# Power_Circuits.net
KiCad netlist of a schematic drawn in Altium Designer
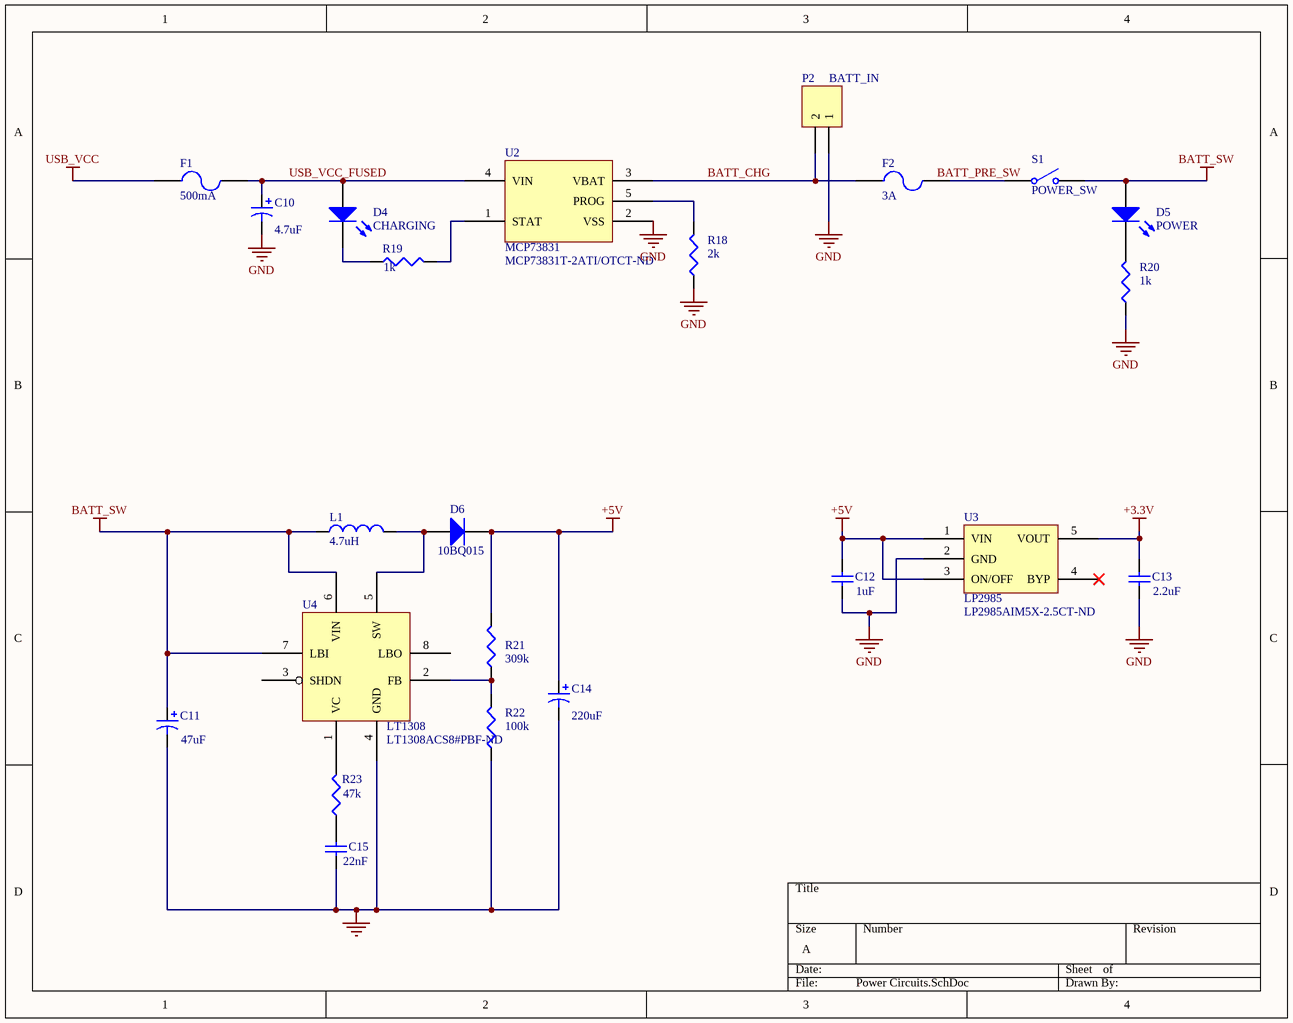
[diagram p0: Power Circuits.SchDoc]

(export (version "E")
  (design (tool "Eeschema 10.0.6"))
  (components
    (comp (ref "C10")
      (value "4.7uF")
      (footprint "TC7343-2917")
      (description "Polarized Capacitor (Surface Mount)")
      (fields (field (name "Comment") "Cap Pol3") (field (name "PUBLISHER") "Altium Limited"))
      (libsource (lib "Miscellaneous Devices") (part "Cap Pol3"))
    )
    (comp (ref "C11")
      (value "47uF")
      (footprint "TC6032-2412")
      (description "Polarized Capacitor (Surface Mount)")
      (fields (field (name "Comment") "Cap Pol3") (field (name "PUBLISHER") "Altium Limited"))
      (libsource (lib "Miscellaneous Devices") (part "Cap Pol3"))
    )
    (comp (ref "C12")
      (value "1uF")
      (footprint "C1206")
      (description "Capacitor (Semiconductor SIM Model)")
      (fields (field (name "Comment") "Cap Semi") (field (name "PUBLISHER") "Altium Limited"))
      (libsource (lib "Miscellaneous Devices") (part "Cap Semi"))
    )
    (comp (ref "C13")
      (value "2.2uF")
      (footprint "C1206")
      (description "Capacitor (Semiconductor SIM Model)")
      (fields (field (name "Comment") "Cap Semi") (field (name "PUBLISHER") "Altium Limited"))
      (libsource (lib "Miscellaneous Devices") (part "Cap Semi"))
    )
    (comp (ref "C14")
      (value "220uF")
      (footprint "TC7343-2917")
      (description "Polarized Capacitor (Surface Mount)")
      (fields (field (name "Comment") "Cap Pol3") (field (name "PUBLISHER") "Altium Limited"))
      (libsource (lib "Miscellaneous Devices") (part "Cap Pol3"))
    )
    (comp (ref "C15")
      (value "22nF")
      (footprint "C1206")
      (description "Capacitor (Semiconductor SIM Model)")
      (fields (field (name "Comment") "Cap Semi") (field (name "PUBLISHER") "Altium Limited"))
      (libsource (lib "Miscellaneous Devices") (part "Cap Semi"))
    )
    (comp (ref "D4")
      (value "CHARGING")
      (footprint "HDR1X2")
      (description "Typical BLUE SiC LED")
      (fields (field (name "PUBLISHER") "Altium Limited"))
      (libsource (lib "Miscellaneous Devices") (part "LED3"))
    )
    (comp (ref "D5")
      (value "POWER")
      (footprint "HDR1X2")
      (description "Typical BLUE SiC LED")
      (fields (field (name "PUBLISHER") "Altium Limited"))
      (libsource (lib "Miscellaneous Devices") (part "LED3"))
    )
    (comp (ref "D6")
      (value "10BQ015")
      (footprint "DSO-C2/X2.3")
      (description "Default Diode")
      (fields (field (name "PUBLISHER") "Altium Limited"))
      (libsource (lib "Miscellaneous Devices") (part "Diode"))
    )
    (comp (ref "F1")
      (value "500mA")
      (footprint "RESC3216M")
      (description "Fuse")
      (fields (field (name "PUBLISHER") "Altium Limited"))
      (libsource (lib "Miscellaneous Devices") (part "Fuse 2"))
    )
    (comp (ref "F2")
      (value "3A")
      (footprint "RESC3216M")
      (description "Fuse")
      (fields (field (name "PUBLISHER") "Altium Limited"))
      (libsource (lib "Miscellaneous Devices") (part "Fuse 2"))
    )
    (comp (ref "L1")
      (value "4.7uH")
      (footprint "MURATA SMT INDUCTOR")
      (description "Inductor")
      (fields (field (name "PUBLISHER") "Altium Limited"))
      (libsource (lib "Miscellaneous Devices") (part "Inductor"))
    )
    (comp (ref "P2")
      (value "BATT_IN")
      (footprint "2MM JST PH - 2 PIN VERT")
      (description "Header, 2-Pin")
      (fields (field (name "PUBLISHER") "Altium Limited"))
      (libsource (lib "Miscellaneous Connectors") (part "Header 2"))
    )
    (comp (ref "R18")
      (value "2k")
      (footprint "RESC3216M")
      (description "Resistor")
      (fields (field (name "Comment") "Res3") (field (name "PUBLISHER") "Altium Limited"))
      (libsource (lib "Miscellaneous Devices") (part "Res3"))
    )
    (comp (ref "R19")
      (value "1k")
      (footprint "RESC3216M")
      (description "Resistor")
      (fields (field (name "Comment") "Res3") (field (name "PUBLISHER") "Altium Limited"))
      (libsource (lib "Miscellaneous Devices") (part "Res3"))
    )
    (comp (ref "R20")
      (value "1k")
      (footprint "RESC3216M")
      (description "Resistor")
      (fields (field (name "Comment") "Res3") (field (name "PUBLISHER") "Altium Limited"))
      (libsource (lib "Miscellaneous Devices") (part "Res3"))
    )
    (comp (ref "R21")
      (value "309k")
      (footprint "RESC3216M")
      (description "Resistor")
      (fields (field (name "Comment") "Res3") (field (name "PUBLISHER") "Altium Limited"))
      (libsource (lib "Miscellaneous Devices") (part "Res3"))
    )
    (comp (ref "R22")
      (value "100k")
      (footprint "RESC3216M")
      (description "Resistor")
      (fields (field (name "Comment") "Res3") (field (name "PUBLISHER") "Altium Limited"))
      (libsource (lib "Miscellaneous Devices") (part "Res3"))
    )
    (comp (ref "R23")
      (value "47k")
      (footprint "RESC3216M")
      (description "Resistor")
      (fields (field (name "Comment") "Res3") (field (name "PUBLISHER") "Altium Limited"))
      (libsource (lib "Miscellaneous Devices") (part "Res3"))
    )
    (comp (ref "S1")
      (value "POWER_SW")
      (footprint "DPDT_PUSHBUTTON_SWITCH")
      (description "Single-Pole, Single-Throw Switch")
      (fields (field (name "PUBLISHER") "Altium Limited"))
      (libsource (lib "Miscellaneous Devices") (part "SW-SPST"))
    )
    (comp (ref "U2")
      (value "MCP73831")
      (footprint "SOT23-5AM")
      (fields (field (name "SUPPLIER PART NUMBER 1") "MCP73831T-2ATI/OTCT-ND"))
      (libsource (lib "Altium Footprints") (part "MCP73831"))
    )
    (comp (ref "U3")
      (value "LP2985")
      (footprint "SOT23-5AM")
      (fields (field (name "SUPPLIER PART NUMBER 1") "LP2985AIM5X-2.5CT-ND"))
      (libsource (lib "Altium Footprints") (part "LP2985"))
    )
    (comp (ref "U4")
      (value "LT1308")
      (footprint "SOIC127P600-8AM")
      (fields (field (name "SUPPLIER PART NUMBER 1") "LT1308ACS8#PBF-ND"))
      (libsource (lib "Altium Footprints") (part "LT1308"))
    )
  )
  (nets
    (net (code "1") (name "+3.3V") (class "Default")
      (node (ref "C13") (pin "2") (pinfunction "2_2") (pintype "passive"))
      (node (ref "U3") (pin "5") (pinfunction "VOUT_5") (pintype "passive"))
    )
    (net (code "2") (name "+5V") (class "Default")
      (node (ref "C12") (pin "2") (pinfunction "2_2") (pintype "passive"))
      (node (ref "C14") (pin "1") (pinfunction "1_1") (pintype "passive"))
      (node (ref "D6") (pin "2") (pinfunction "K_2") (pintype "passive"))
      (node (ref "R21") (pin "2") (pinfunction "2_2") (pintype "passive"))
      (node (ref "U3") (pin "1") (pinfunction "VIN_1") (pintype "passive"))
      (node (ref "U3") (pin "3") (pinfunction "ON/OFF_3") (pintype "passive"))
    )
    (net (code "3") (name "/BATT_CHG") (class "Default")
      (node (ref "F2") (pin "1") (pinfunction "1_1") (pintype "passive"))
      (node (ref "P2") (pin "2") (pinfunction "2_2") (pintype "passive"))
      (node (ref "U2") (pin "3") (pinfunction "VBAT_3") (pintype "passive"))
    )
    (net (code "5") (name "/USB_VCC_FUSED") (class "Default")
      (node (ref "C10") (pin "1") (pinfunction "1_1") (pintype "passive"))
      (node (ref "D4") (pin "1") (pinfunction "A_1") (pintype "passive"))
      (node (ref "F1") (pin "2") (pinfunction "2_2") (pintype "passive"))
      (node (ref "U2") (pin "4") (pinfunction "VIN_4") (pintype "passive"))
    )
    (net (code "6") (name "BATT_SW") (class "Default")
      (node (ref "C11") (pin "1") (pinfunction "1_1") (pintype "passive"))
      (node (ref "D5") (pin "1") (pinfunction "A_1") (pintype "passive"))
      (node (ref "L1") (pin "1") (pinfunction "1_1") (pintype "passive"))
      (node (ref "S1") (pin "2") (pinfunction "NO_2") (pintype "passive"))
      (node (ref "U4") (pin "6") (pinfunction "VIN_6") (pintype "passive"))
      (node (ref "U4") (pin "7") (pinfunction "LBI_7") (pintype "passive"))
    )
    (net (code "7") (name "GND") (class "Default")
      (node (ref "C10") (pin "2") (pinfunction "2_2") (pintype "passive"))
      (node (ref "C11") (pin "2") (pinfunction "2_2") (pintype "passive"))
      (node (ref "C12") (pin "1") (pinfunction "1_1") (pintype "passive"))
      (node (ref "C13") (pin "1") (pinfunction "1_1") (pintype "passive"))
      (node (ref "C14") (pin "2") (pinfunction "2_2") (pintype "passive"))
      (node (ref "C15") (pin "1") (pinfunction "1_1") (pintype "passive"))
      (node (ref "P2") (pin "1") (pinfunction "1_1") (pintype "passive"))
      (node (ref "R18") (pin "1") (pinfunction "1_1") (pintype "passive"))
      (node (ref "R20") (pin "1") (pinfunction "1_1") (pintype "passive"))
      (node (ref "R22") (pin "1") (pinfunction "1_1") (pintype "passive"))
      (node (ref "U2") (pin "2") (pinfunction "VSS_2") (pintype "passive"))
      (node (ref "U3") (pin "2") (pinfunction "GND_2") (pintype "passive"))
      (node (ref "U4") (pin "4") (pinfunction "GND_4") (pintype "passive"))
    )
    (net (code "8") (name "Net-(C15-Pad2)") (class "Default")
      (node (ref "C15") (pin "2") (pinfunction "2_2") (pintype "passive"))
      (node (ref "R23") (pin "1") (pinfunction "1_1") (pintype "passive"))
    )
    (net (code "9") (name "Net-(D4-K)") (class "Default")
      (node (ref "D4") (pin "2") (pinfunction "K_2") (pintype "passive"))
      (node (ref "R19") (pin "1") (pinfunction "1_1") (pintype "passive"))
    )
    (net (code "10") (name "Net-(D5-K)") (class "Default")
      (node (ref "D5") (pin "2") (pinfunction "K_2") (pintype "passive"))
      (node (ref "R20") (pin "2") (pinfunction "2_2") (pintype "passive"))
    )
    (net (code "11") (name "Net-(D6-A)") (class "Default")
      (node (ref "D6") (pin "1") (pinfunction "A_1") (pintype "passive"))
      (node (ref "L1") (pin "2") (pinfunction "2_2") (pintype "passive"))
      (node (ref "U4") (pin "5") (pinfunction "SW_5") (pintype "passive"))
    )
    (net (code "12") (name "Net-(S1-COMMON)") (class "Default")
      (node (ref "F2") (pin "2") (pinfunction "2_2") (pintype "passive"))
      (node (ref "S1") (pin "1") (pinfunction "COMMON_1") (pintype "passive"))
    )
    (net (code "13") (name "Net-(U2-PROG)") (class "Default")
      (node (ref "R18") (pin "2") (pinfunction "2_2") (pintype "passive"))
      (node (ref "U2") (pin "5") (pinfunction "PROG_5") (pintype "passive"))
    )
    (net (code "14") (name "Net-(U2-STAT)") (class "Default")
      (node (ref "R19") (pin "2") (pinfunction "2_2") (pintype "passive"))
      (node (ref "U2") (pin "1") (pinfunction "STAT_1") (pintype "passive"))
    )
    (net (code "15") (name "Net-(U4-FB)") (class "Default")
      (node (ref "R21") (pin "1") (pinfunction "1_1") (pintype "passive"))
      (node (ref "R22") (pin "2") (pinfunction "2_2") (pintype "passive"))
      (node (ref "U4") (pin "2") (pinfunction "FB_2") (pintype "passive"))
    )
    (net (code "16") (name "Net-(U4-VC)") (class "Default")
      (node (ref "R23") (pin "2") (pinfunction "2_2") (pintype "passive"))
      (node (ref "U4") (pin "1") (pinfunction "VC_1") (pintype "passive"))
    )
    (net (code "17") (name "USB_VCC") (class "Default")
      (node (ref "F1") (pin "1") (pinfunction "1_1") (pintype "passive"))
    )
    (net (code "18") (name "unconnected-(U3-BYP-Pad4)") (class "Default")
      (node (ref "U3") (pin "4") (pinfunction "BYP_4") (pintype "passive+no_connect"))
    )
    (net (code "19") (name "unconnected-(U4-LBO-Pad8)") (class "Default")
      (node (ref "U4") (pin "8") (pinfunction "LBO_8") (pintype "passive"))
    )
    (net (code "20") (name "unconnected-(U4-SHDN-Pad3)") (class "Default")
      (node (ref "U4") (pin "3") (pinfunction "SHDN_3") (pintype "passive"))
    )
  )
)
